# Astable_multivibrator_using_555.net
KiCad netlist of a schematic drawn in EAGLE
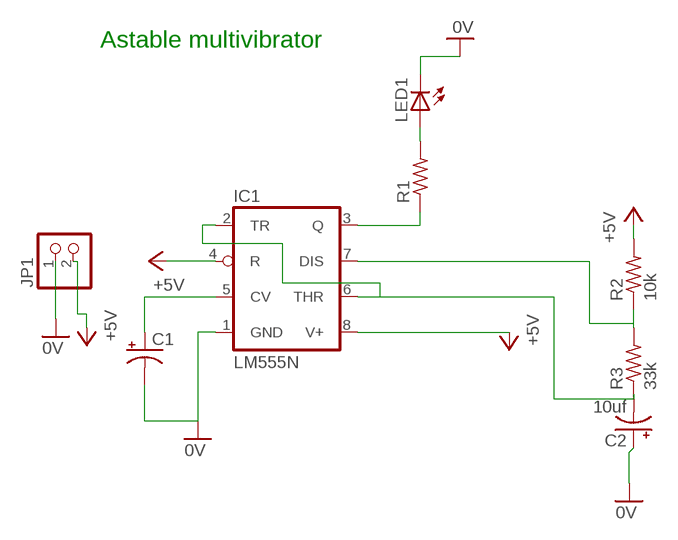
[diagram p0: schematic, sheet 1]

(export (version "E")
  (design (tool "Eeschema 10.0.6"))
  (components
    (comp (ref "C1")
      (value "CPOL-USE3.5-10")
      (footprint "eagle-import:E3,5-10")
      (libsource (lib "eagle-import") (part "CPOL-USE3.5-10"))
    )
    (comp (ref "C2")
      (value "10uf")
      (footprint "eagle-import:E3,5-10")
      (libsource (lib "eagle-import") (part "CPOL-USE3.5-10"))
    )
    (comp (ref "IC1")
      (value "LM555N")
      (footprint "eagle-import:DIL08")
      (libsource (lib "eagle-import") (part "555NLM"))
    )
    (comp (ref "JP1")
      (value "PINHD-1X2")
      (footprint "eagle-import:1X02")
      (libsource (lib "eagle-import") (part "PINHD-1X2"))
    )
    (comp (ref "LED1")
      (value "LED5MM")
      (footprint "eagle-import:LED5MM")
      (libsource (lib "eagle-import") (part "LED5MM"))
    )
    (comp (ref "R1")
      (value "R-US_0207/10")
      (footprint "eagle-import:0207_10")
      (libsource (lib "eagle-import") (part "R-US_0207/10"))
    )
    (comp (ref "R2")
      (value "10k")
      (footprint "eagle-import:0207_10")
      (libsource (lib "eagle-import") (part "R-US_0207/10"))
    )
    (comp (ref "R3")
      (value "33k")
      (footprint "eagle-import:0207_10")
      (libsource (lib "eagle-import") (part "R-US_0207/10"))
    )
  )
  (nets
    (net (code "1") (name "+5V") (class "Default")
      (node (ref "IC1") (pin "4") (pinfunction "R_4") (pintype "input"))
      (node (ref "IC1") (pin "8") (pinfunction "V+_8") (pintype "power_in"))
      (node (ref "JP1") (pin "2") (pinfunction "2_2") (pintype "passive"))
      (node (ref "R2") (pin "2") (pinfunction "2_2") (pintype "passive"))
    )
    (net (code "2") (name "0V") (class "Default")
      (node (ref "C1") (pin "-") (pinfunction "-_-") (pintype "passive"))
      (node (ref "C2") (pin "+") (pinfunction "+_+") (pintype "passive"))
      (node (ref "IC1") (pin "1") (pinfunction "GND_1") (pintype "power_in"))
      (node (ref "JP1") (pin "1") (pinfunction "1_1") (pintype "passive"))
      (node (ref "LED1") (pin "K") (pinfunction "C_K") (pintype "passive"))
    )
    (net (code "3") (name "Net-(IC1-CV)") (class "Default")
      (node (ref "C1") (pin "+") (pinfunction "+_+") (pintype "passive"))
      (node (ref "IC1") (pin "5") (pinfunction "CV_5") (pintype "input"))
    )
    (net (code "4") (name "Net-(IC1-DIS)") (class "Default")
      (node (ref "IC1") (pin "7") (pinfunction "DIS_7") (pintype "input"))
      (node (ref "R2") (pin "1") (pinfunction "1_1") (pintype "passive"))
      (node (ref "R3") (pin "2") (pinfunction "2_2") (pintype "passive"))
    )
    (net (code "5") (name "Net-(IC1-Q)") (class "Default")
      (node (ref "IC1") (pin "3") (pinfunction "Q_3") (pintype "output"))
      (node (ref "R1") (pin "1") (pinfunction "1_1") (pintype "passive"))
    )
    (net (code "6") (name "Net-(IC1-THR)") (class "Default")
      (node (ref "C2") (pin "-") (pinfunction "-_-") (pintype "passive"))
      (node (ref "IC1") (pin "2") (pinfunction "TR_2") (pintype "input"))
      (node (ref "IC1") (pin "6") (pinfunction "THR_6") (pintype "input"))
      (node (ref "R3") (pin "1") (pinfunction "1_1") (pintype "passive"))
    )
    (net (code "7") (name "Net-(LED1-PadA)") (class "Default")
      (node (ref "LED1") (pin "A") (pinfunction "A_A") (pintype "passive"))
      (node (ref "R1") (pin "2") (pinfunction "2_2") (pintype "passive"))
    )
  )
)
